# MCU.net
KiCad netlist of a schematic drawn in Altium Designer
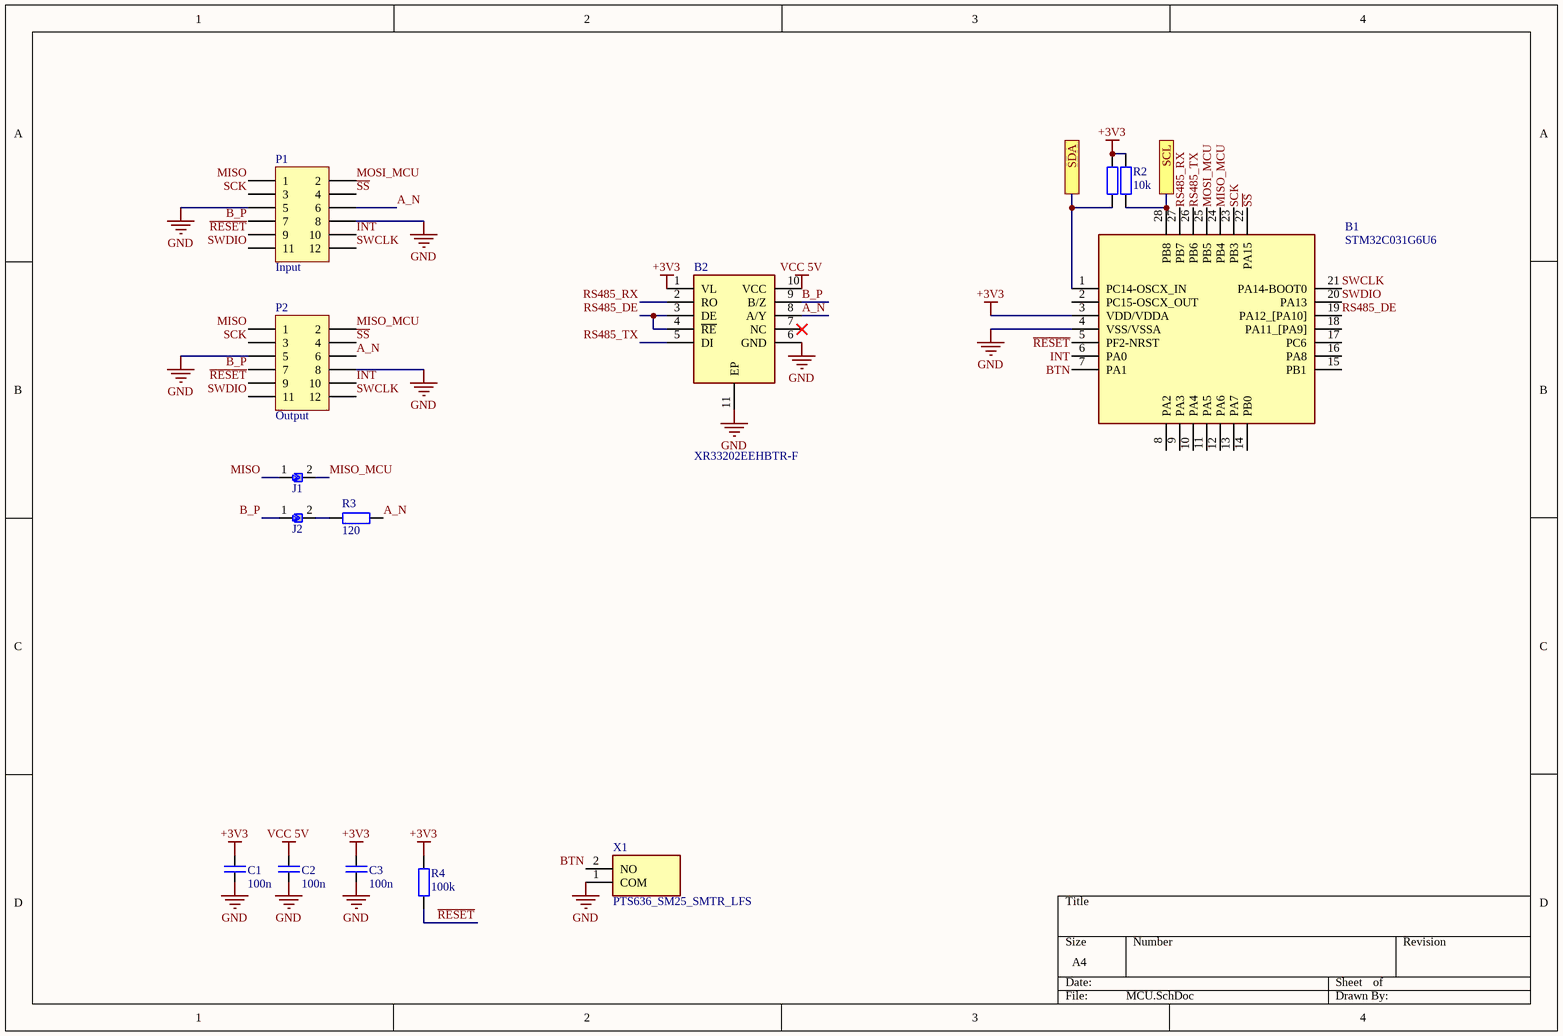
[diagram p0: MCU.SchDoc]

(export (version "E")
  (design (tool "Eeschema 10.0.6"))
  (components
    (comp (ref "B1")
      (value "STM32C031G6U6")
      (footprint "QFN50P400X400X60-28N-D")
      (fields (field (name "MOUSER PART NUMBER") "511-STM32C031G6U6"))
      (libsource (lib "components_library") (part "STM32C031G6U6"))
    )
    (comp (ref "B2")
      (value "XR33202EEHBTR-F")
      (footprint "SON50P300X300X80-11N-D")
      (description "RS-422/RS-485 Interface IC Wide Supply Trans with I/O Interface")
      (fields (field (name "MOUSER PART NUMBER") "701-XR33202EEHBTR-F"))
      (libsource (lib "components_library") (part "XR33202EEHBTR-F"))
    )
    (comp (ref "C1")
      (value "100n")
      (footprint "R1005_0402i_L")
      (description "Capacitor")
      (libsource (lib "General") (part "C"))
    )
    (comp (ref "C2")
      (value "100n")
      (footprint "R1005_0402i_L")
      (description "Capacitor")
      (libsource (lib "General") (part "C"))
    )
    (comp (ref "C3")
      (value "100n")
      (footprint "R1005_0402i_L")
      (description "Capacitor")
      (libsource (lib "General") (part "C"))
    )
    (comp (ref "J1")
      (value "solder_jumper")
      (footprint "solder_jumper_triangle")
      (libsource (lib "components_library") (part "solder_jumper"))
    )
    (comp (ref "J2")
      (value "solder_jumper")
      (footprint "solder_jumper_triangle")
      (libsource (lib "components_library") (part "solder_jumper"))
    )
    (comp (ref "P1")
      (value "Input")
      (footprint "1.27mm SMD conn")
      (description "Header, 6-Pin, Dual row")
      (fields (field (name "PUBLISHER") "Altium Limited"))
      (libsource (lib "Miscellaneous Connectors") (part "Header 6X2"))
    )
    (comp (ref "P2")
      (value "Output")
      (footprint "1.27mm SMD conn")
      (description "Header, 6-Pin, Dual row")
      (fields (field (name "PUBLISHER") "Altium Limited"))
      (libsource (lib "Miscellaneous Connectors") (part "Header 6X2"))
    )
    (comp (ref "R1")
      (value "10k")
      (footprint "R1005_0402i_L")
      (description "R")
      (libsource (lib "General") (part "R"))
    )
    (comp (ref "R2")
      (value "10k")
      (footprint "R1005_0402i_L")
      (description "R")
      (libsource (lib "General") (part "R"))
    )
    (comp (ref "R3")
      (value "120")
      (footprint "R1005_0402i_L")
      (description "R")
      (libsource (lib "General") (part "R"))
    )
    (comp (ref "R4")
      (value "100k")
      (footprint "R1005_0402i_L")
      (description "R")
      (libsource (lib "General") (part "R"))
    )
    (comp (ref "X1")
      (value "PTS636_SM25_SMTR_LFS")
      (footprint "PTS636SM25SMTRLFS")
      (description "Tactile Switches Tact 50mA 12VDC, 6.0x3.5, 2.5mm H, 180gf, G leads, No ground pin, White Actuator")
      (fields
        (field (name "MOUSER PART NUMBER") "611-PTS636SM25SMTRLF")
        (field (name "MANUFACTURER_PART_NUMBER") "PTS636 SM25 SMTR LFS")
      )
      (libsource (lib "components_library") (part "PTS636_SM25_SMTR_LFS"))
    )
  )
  (nets
    (net (code "1") (name "+3V3") (class "Default")
      (node (ref "B1") (pin "3") (pinfunction "VDD/VDDA_3") (pintype "passive"))
      (node (ref "B2") (pin "1") (pinfunction "VL_1") (pintype "passive"))
      (node (ref "C1") (pin "1") (pinfunction "1_1") (pintype "passive"))
      (node (ref "C3") (pin "1") (pinfunction "1_1") (pintype "passive"))
      (node (ref "R1") (pin "1") (pintype "passive"))
      (node (ref "R2") (pin "1") (pintype "passive"))
      (node (ref "R4") (pin "1") (pintype "passive"))
    )
    (net (code "2") (name "/A_N") (class "Default")
      (node (ref "B2") (pin "8") (pinfunction "A/Y_8") (pintype "passive"))
      (node (ref "P1") (pin "6") (pinfunction "6_6") (pintype "passive"))
      (node (ref "P2") (pin "6") (pinfunction "6_6") (pintype "passive"))
      (node (ref "R3") (pin "2") (pintype "passive"))
    )
    (net (code "3") (name "/BTN") (class "Default")
      (node (ref "B1") (pin "7") (pinfunction "PA1_7") (pintype "passive"))
      (node (ref "X1") (pin "2") (pinfunction "NO_2") (pintype "passive"))
    )
    (net (code "4") (name "/B_P") (class "Default")
      (node (ref "B2") (pin "9") (pinfunction "B/Z_9") (pintype "passive"))
      (node (ref "J2") (pin "1") (pintype "passive"))
      (node (ref "P1") (pin "7") (pinfunction "7_7") (pintype "passive"))
      (node (ref "P2") (pin "7") (pinfunction "7_7") (pintype "passive"))
    )
    (net (code "5") (name "/INT") (class "Default")
      (node (ref "B1") (pin "6") (pinfunction "PA0_6") (pintype "passive"))
      (node (ref "P1") (pin "10") (pinfunction "10_10") (pintype "passive"))
      (node (ref "P2") (pin "10") (pinfunction "10_10") (pintype "passive"))
    )
    (net (code "6") (name "/MISO") (class "Default")
      (node (ref "J1") (pin "1") (pintype "passive"))
      (node (ref "P1") (pin "1") (pinfunction "1_1") (pintype "passive"))
      (node (ref "P2") (pin "1") (pinfunction "1_1") (pintype "passive"))
    )
    (net (code "7") (name "/MISO_MCU") (class "Default")
      (node (ref "B1") (pin "24") (pinfunction "PB4_24") (pintype "passive"))
      (node (ref "J1") (pin "2") (pintype "passive"))
      (node (ref "P2") (pin "2") (pinfunction "2_2") (pintype "passive"))
    )
    (net (code "8") (name "/MOSI_MCU") (class "Default")
      (node (ref "B1") (pin "25") (pinfunction "PB5_25") (pintype "passive"))
      (node (ref "P1") (pin "2") (pinfunction "2_2") (pintype "passive"))
    )
    (net (code "9") (name "/RS485_DE") (class "Default")
      (node (ref "B1") (pin "19") (pinfunction "PA12_[PA10]_19") (pintype "passive"))
      (node (ref "B2") (pin "3") (pinfunction "DE_3") (pintype "passive"))
      (node (ref "B2") (pin "4") (pinfunction "~{RE}_4") (pintype "passive"))
    )
    (net (code "10") (name "/RS485_RX") (class "Default")
      (node (ref "B1") (pin "27") (pinfunction "PB7_27") (pintype "passive"))
      (node (ref "B2") (pin "2") (pinfunction "RO_2") (pintype "passive"))
    )
    (net (code "11") (name "/RS485_TX") (class "Default")
      (node (ref "B1") (pin "26") (pinfunction "PB6_26") (pintype "passive"))
      (node (ref "B2") (pin "5") (pinfunction "DI_5") (pintype "passive"))
    )
    (net (code "12") (name "/SCK") (class "Default")
      (node (ref "B1") (pin "23") (pinfunction "PB3_23") (pintype "passive"))
      (node (ref "P1") (pin "3") (pinfunction "3_3") (pintype "passive"))
      (node (ref "P2") (pin "3") (pinfunction "3_3") (pintype "passive"))
    )
    (net (code "13") (name "/SCL") (class "Default")
      (node (ref "B1") (pin "28") (pinfunction "PB8_28") (pintype "passive"))
      (node (ref "R2") (pin "2") (pintype "passive"))
    )
    (net (code "14") (name "/SDA") (class "Default")
      (node (ref "B1") (pin "1") (pinfunction "PC14-OSCX_IN_1") (pintype "passive"))
      (node (ref "R1") (pin "2") (pintype "passive"))
    )
    (net (code "15") (name "/SWCLK") (class "Default")
      (node (ref "B1") (pin "21") (pinfunction "PA14-BOOT0_21") (pintype "passive"))
      (node (ref "P1") (pin "12") (pinfunction "12_12") (pintype "passive"))
      (node (ref "P2") (pin "12") (pinfunction "12_12") (pintype "passive"))
    )
    (net (code "16") (name "/SWDIO") (class "Default")
      (node (ref "B1") (pin "20") (pinfunction "PA13_20") (pintype "passive"))
      (node (ref "P1") (pin "11") (pinfunction "11_11") (pintype "passive"))
      (node (ref "P2") (pin "11") (pinfunction "11_11") (pintype "passive"))
    )
    (net (code "17") (name "/~{RESET}") (class "Default")
      (node (ref "B1") (pin "5") (pinfunction "PF2-NRST_5") (pintype "passive"))
      (node (ref "P1") (pin "9") (pinfunction "9_9") (pintype "passive"))
      (node (ref "P2") (pin "9") (pinfunction "9_9") (pintype "passive"))
      (node (ref "R4") (pin "2") (pintype "passive"))
    )
    (net (code "18") (name "/~{SS}") (class "Default")
      (node (ref "B1") (pin "22") (pinfunction "PA15_22") (pintype "passive"))
      (node (ref "P1") (pin "4") (pinfunction "4_4") (pintype "passive"))
      (node (ref "P2") (pin "4") (pinfunction "4_4") (pintype "passive"))
    )
    (net (code "19") (name "GND") (class "Default")
      (node (ref "B1") (pin "4") (pinfunction "VSS/VSSA_4") (pintype "passive"))
      (node (ref "B2") (pin "11") (pinfunction "EP_11") (pintype "passive"))
      (node (ref "B2") (pin "6") (pinfunction "GND_6") (pintype "passive"))
      (node (ref "C1") (pin "2") (pinfunction "2_2") (pintype "passive"))
      (node (ref "C2") (pin "2") (pinfunction "2_2") (pintype "passive"))
      (node (ref "C3") (pin "2") (pinfunction "2_2") (pintype "passive"))
      (node (ref "P1") (pin "5") (pinfunction "5_5") (pintype "passive"))
      (node (ref "P1") (pin "8") (pinfunction "8_8") (pintype "passive"))
      (node (ref "P2") (pin "5") (pinfunction "5_5") (pintype "passive"))
      (node (ref "P2") (pin "8") (pinfunction "8_8") (pintype "passive"))
      (node (ref "X1") (pin "1") (pinfunction "COM_1") (pintype "passive"))
    )
    (net (code "20") (name "Net-(J2-Pad2)") (class "Default")
      (node (ref "J2") (pin "2") (pintype "passive"))
      (node (ref "R3") (pin "1") (pintype "passive"))
    )
    (net (code "21") (name "VCC 5V") (class "Default")
      (node (ref "B2") (pin "10") (pinfunction "VCC_10") (pintype "passive"))
      (node (ref "C2") (pin "1") (pinfunction "1_1") (pintype "passive"))
    )
    (net (code "22") (name "unconnected-(B1-PA2-Pad8)") (class "Default")
      (node (ref "B1") (pin "8") (pinfunction "PA2_8") (pintype "passive"))
    )
    (net (code "23") (name "unconnected-(B1-PA3-Pad9)") (class "Default")
      (node (ref "B1") (pin "9") (pinfunction "PA3_9") (pintype "passive"))
    )
    (net (code "24") (name "unconnected-(B1-PA4-Pad10)") (class "Default")
      (node (ref "B1") (pin "10") (pinfunction "PA4_10") (pintype "passive"))
    )
    (net (code "25") (name "unconnected-(B1-PA5-Pad11)") (class "Default")
      (node (ref "B1") (pin "11") (pinfunction "PA5_11") (pintype "passive"))
    )
    (net (code "26") (name "unconnected-(B1-PA6-Pad12)") (class "Default")
      (node (ref "B1") (pin "12") (pinfunction "PA6_12") (pintype "passive"))
    )
    (net (code "27") (name "unconnected-(B1-PA7-Pad13)") (class "Default")
      (node (ref "B1") (pin "13") (pinfunction "PA7_13") (pintype "passive"))
    )
    (net (code "28") (name "unconnected-(B1-PA8-Pad16)") (class "Default")
      (node (ref "B1") (pin "16") (pinfunction "PA8_16") (pintype "passive"))
    )
    (net (code "29") (name "unconnected-(B1-PA11_[PA9]-Pad18)") (class "Default")
      (node (ref "B1") (pin "18") (pinfunction "PA11_[PA9]_18") (pintype "passive"))
    )
    (net (code "30") (name "unconnected-(B1-PB0-Pad14)") (class "Default")
      (node (ref "B1") (pin "14") (pinfunction "PB0_14") (pintype "passive"))
    )
    (net (code "31") (name "unconnected-(B1-PB1-Pad15)") (class "Default")
      (node (ref "B1") (pin "15") (pinfunction "PB1_15") (pintype "passive"))
    )
    (net (code "32") (name "unconnected-(B1-PC6-Pad17)") (class "Default")
      (node (ref "B1") (pin "17") (pinfunction "PC6_17") (pintype "passive"))
    )
    (net (code "33") (name "unconnected-(B1-PC15-OSCX_OUT-Pad2)") (class "Default")
      (node (ref "B1") (pin "2") (pinfunction "PC15-OSCX_OUT_2") (pintype "passive"))
    )
    (net (code "34") (name "unconnected-(B2-NC-Pad7)") (class "Default")
      (node (ref "B2") (pin "7") (pinfunction "NC_7") (pintype "passive+no_connect"))
    )
  )
)
